# SCH_3Electronic-Trash_2025-03-29.net
KiCad netlist of a schematic drawn in EasyEDA
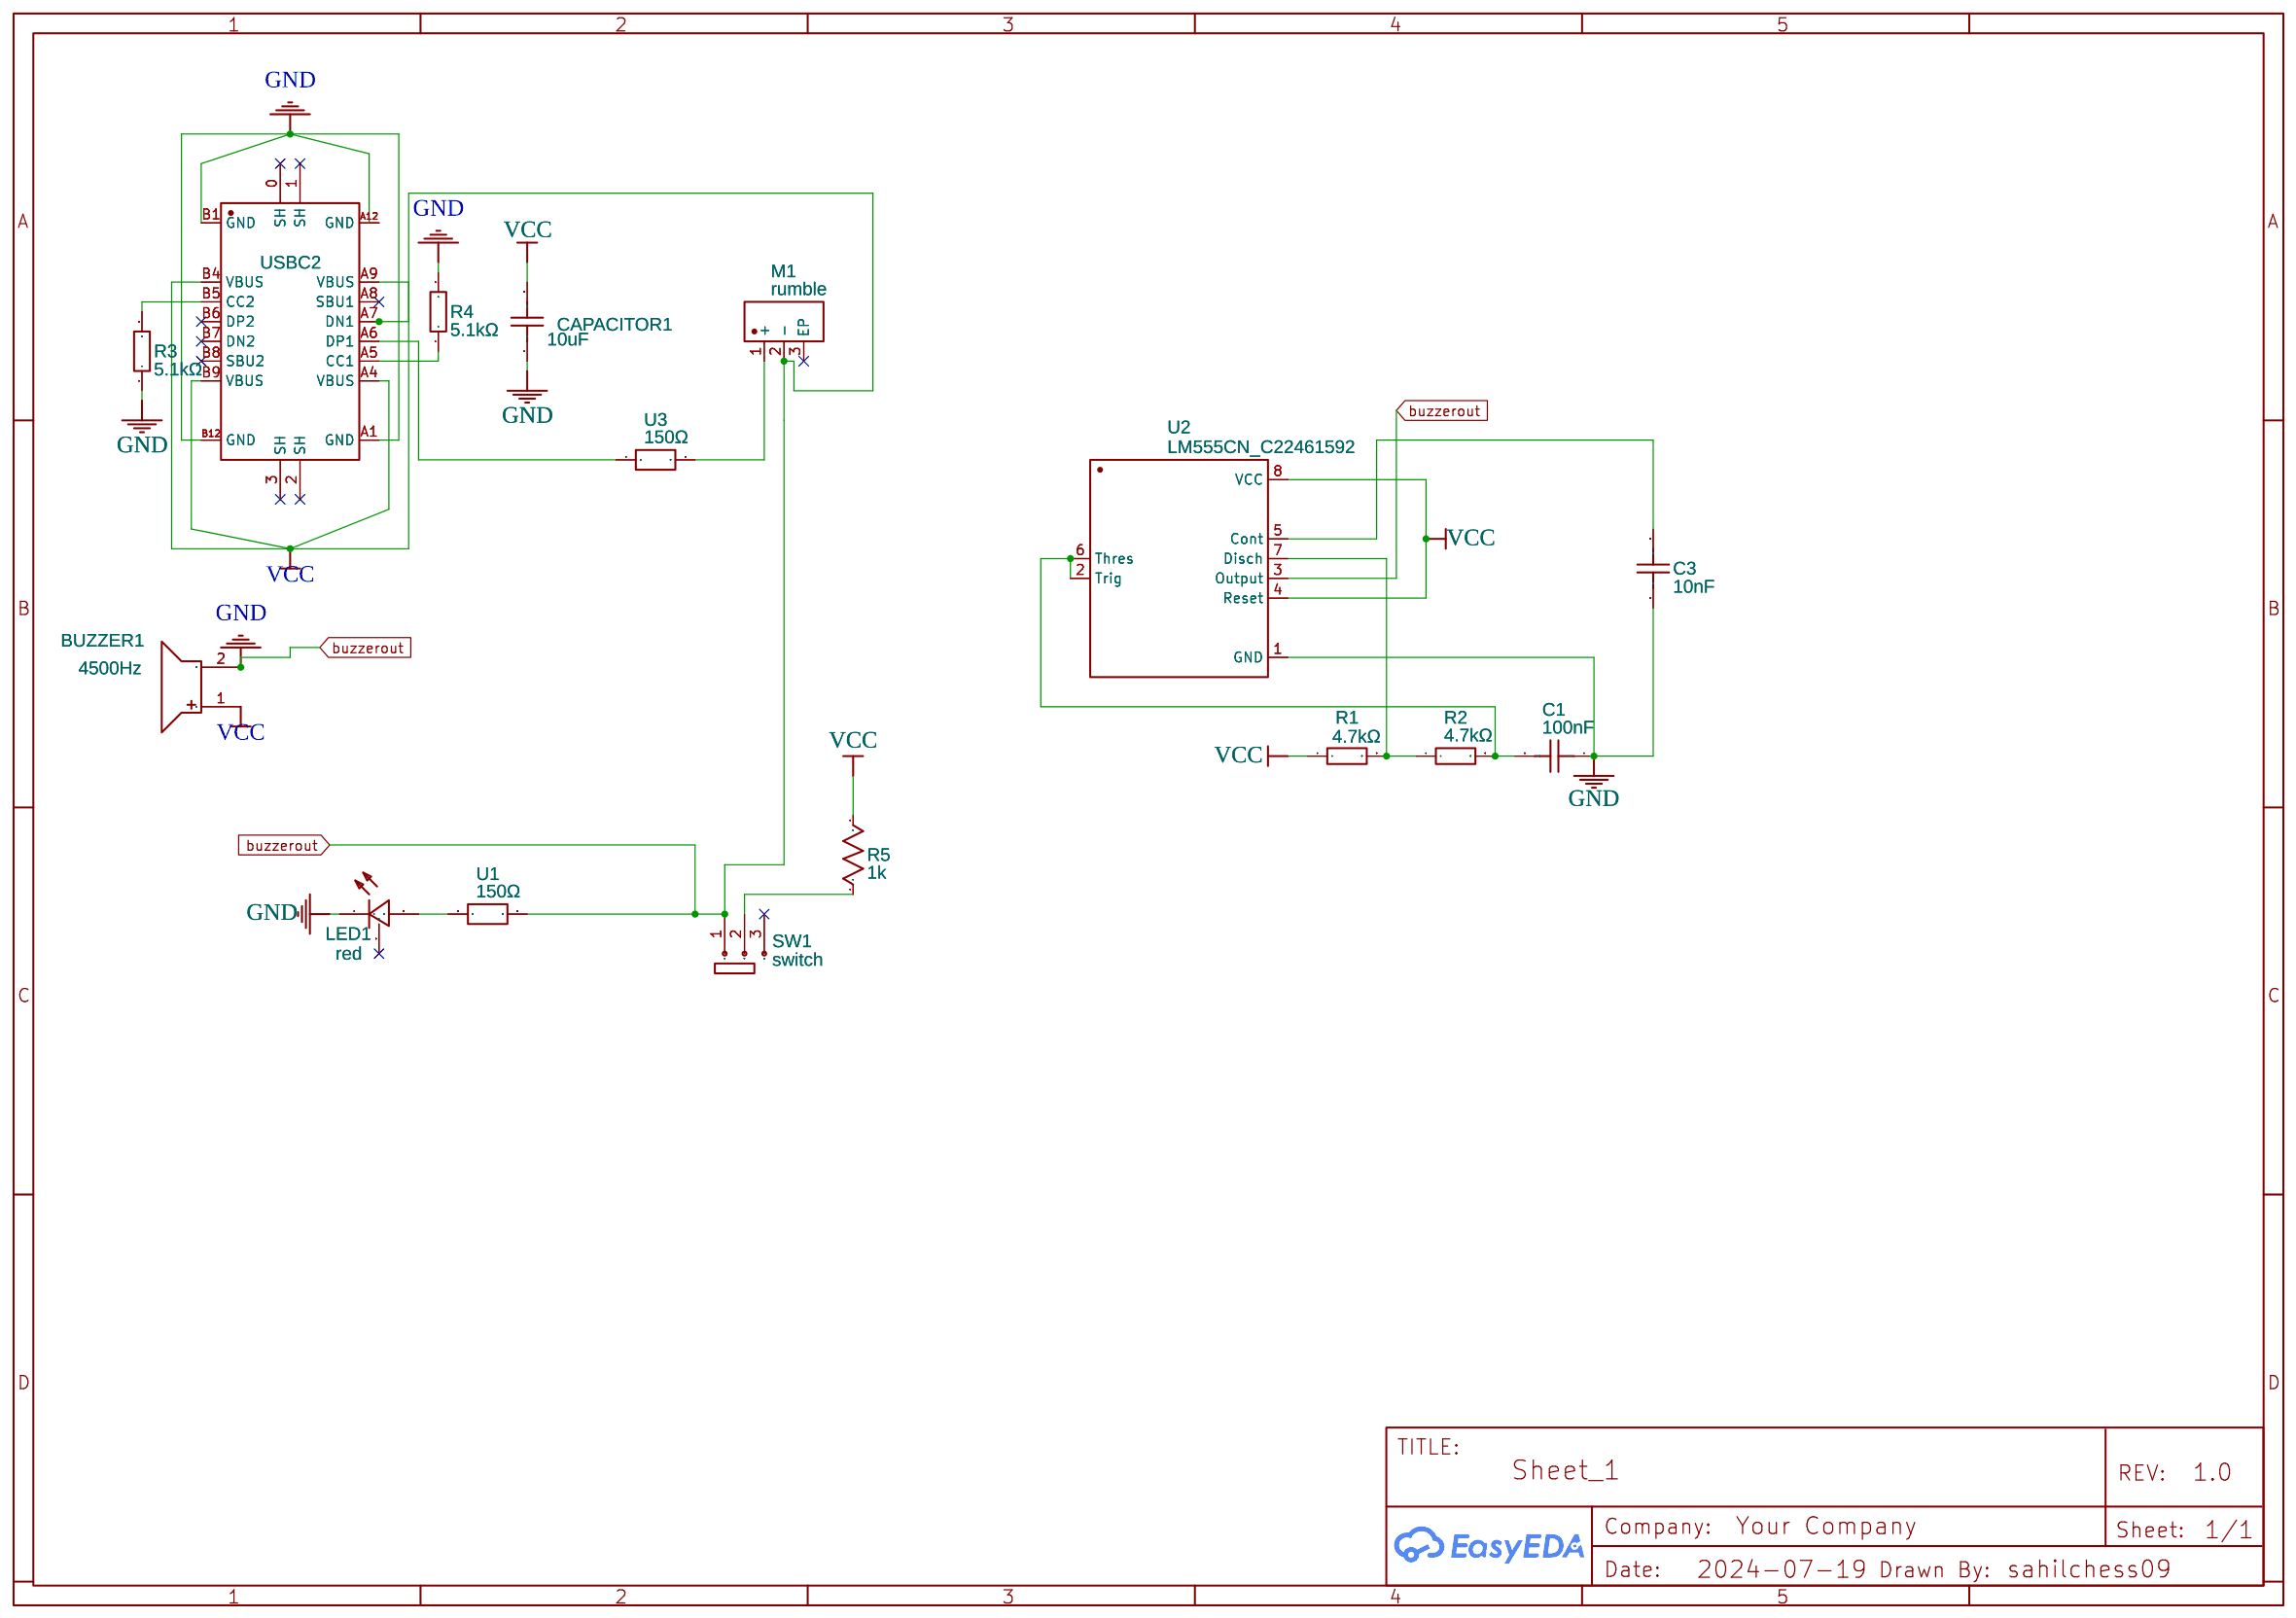
[diagram p0: schematic sheet]

(export (version "E")
  (design (tool "Eeschema 10.0.6"))
  (components
    (comp (ref "BUZZER1")
      (value "4500Hz")
      (fields (field (name "Manufacturer Part") "HND-1407B") (field (name "Manufacturer") "华能"))
      (libsource (lib "") (part "HND-1407B"))
    )
    (comp (ref "C1")
      (value "100nF")
      (fields
        (field (name "Manufacturer Part") "MPX104K31D2KN15800")
        (field (name "Manufacturer") "KNSCHA(科尼盛)")
      )
      (libsource (lib "") (part "MPX104K31D2KN15800"))
    )
    (comp (ref "C3")
      (value "10nF")
      (fields
        (field (name "Manufacturer Part") "B1030630-D-10-3R")
        (field (name "Manufacturer") "GDHY(广东华裕)")
      )
      (libsource (lib "") (part "B1030630-D-10-3R"))
    )
    (comp (ref "CAPACITOR1")
      (value "10uF")
      (fields
        (field (name "Manufacturer Part") "CL10A106KP8NNNC")
        (field (name "Manufacturer") "SAMSUNG(三星)")
      )
      (libsource (lib "") (part "CL10A106KP8NNNC"))
    )
    (comp (ref "LED1")
      (value "red")
      (fields
        (field (name "Manufacturer Part") "TJ-S3210SW5TGLC2R-A5")
        (field (name "Manufacturer") "TOGIALED(统佳)")
      )
      (libsource (lib "") (part "TJ-S3210SW5TGLC2R-A5"))
    )
    (comp (ref "M1")
      (value "rumble")
      (fields (field (name "Manufacturer Part") "Z3OC1T8219731") (field (name "Manufacturer") "KOTL(金龙机电)"))
      (libsource (lib "") (part "Z3OC1T8219731"))
    )
    (comp (ref "R1")
      (value "4.7kΩ")
      (fields
        (field (name "Manufacturer Part") "MF1/4W-4.7KΩ±1% T")
        (field (name "Manufacturer") "CCO(千志电子)")
      )
      (libsource (lib "") (part "MF1/4W-4.7KΩ±1% T52"))
    )
    (comp (ref "R2")
      (value "4.7kΩ")
      (fields
        (field (name "Manufacturer Part") "MF1/4W-4.7KΩ±1% T")
        (field (name "Manufacturer") "CCO(千志电子)")
      )
      (libsource (lib "") (part "MF1/4W-4.7KΩ±1% T52"))
    )
    (comp (ref "R3")
      (value "5.1kΩ")
      (fields (field (name "Manufacturer Part") "RMC08055.1K1%N") (field (name "Manufacturer") "Tyohm(幸亚电阻)"))
      (libsource (lib "") (part "RMC08055.1K1%N"))
    )
    (comp (ref "R4")
      (value "5.1kΩ")
      (fields (field (name "Manufacturer Part") "RMC08055.1K1%N") (field (name "Manufacturer") "Tyohm(幸亚电阻)"))
      (libsource (lib "") (part "RMC08055.1K1%N"))
    )
    (comp (ref "R5") (value "1k") (libsource (lib "") (part "R_0603_US")))
    (comp (ref "SW1")
      (value "switch")
      (fields (field (name "Manufacturer Part") "K3-1235S-L1") (field (name "Manufacturer") "韩国韩荣"))
      (libsource (lib "") (part "K3-1235S-L1"))
    )
    (comp (ref "U1")
      (value "150Ω")
      (fields
        (field (name "Manufacturer Part") "TNPW0402150RBYEP")
        (field (name "Manufacturer") "VISHAY(威世)")
      )
      (libsource (lib "") (part "TNPW0402150RBYEP"))
    )
    (comp (ref "U2")
      (value "LM555CN_C22461592")
      (fields (field (name "Manufacturer Part") "LM555CN") (field (name "Manufacturer") "HGSEMI(华冠)"))
      (libsource (lib "") (part "LM555CN_C22461592"))
    )
    (comp (ref "U3")
      (value "150Ω")
      (fields
        (field (name "Manufacturer Part") "TNPW0402150RBYEP")
        (field (name "Manufacturer") "VISHAY(威世)")
      )
      (libsource (lib "") (part "TNPW0402150RBYEP"))
    )
    (comp (ref "USBC2")
      (value "TYPE-C-31-M-12")
      (fields (field (name "Manufacturer") "韩国韩荣"))
      (libsource (lib "") (part "TYPE-C-31-M-12"))
    )
  )
  (nets
    (net (code "1") (name "Net-(LED1-Pad2)") (class "Default")
      (node (ref "LED1") (pin "2") (pinfunction "2_2") (pintype "unspecified"))
      (node (ref "U1") (pin "1") (pinfunction "1_1") (pintype "unspecified"))
    )
    (net (code "2") (name "Net-(M1-+)") (class "Default")
      (node (ref "M1") (pin "1") (pinfunction "+_1") (pintype "unspecified"))
      (node (ref "U3") (pin "2") (pinfunction "2_2") (pintype "unspecified"))
    )
    (net (code "3") (name "Net-(R5-Pad1)") (class "Default")
      (node (ref "R5") (pin "1") (pinfunction "1_1") (pintype "unspecified"))
      (node (ref "SW1") (pin "2") (pinfunction "2_2") (pintype "unspecified"))
    )
    (net (code "4") (name "Net-(U2-Cont)") (class "Default")
      (node (ref "C3") (pin "2") (pinfunction "2_2") (pintype "unspecified"))
      (node (ref "U2") (pin "5") (pinfunction "Cont_5") (pintype "unspecified"))
    )
    (net (code "5") (name "Net-(U2-Disch)") (class "Default")
      (node (ref "R1") (pin "2") (pinfunction "2_2") (pintype "unspecified"))
      (node (ref "R2") (pin "1") (pinfunction "1_1") (pintype "unspecified"))
      (node (ref "U2") (pin "7") (pinfunction "Disch_7") (pintype "unspecified"))
    )
    (net (code "6") (name "Net-(U2-Thres)") (class "Default")
      (node (ref "C1") (pin "2") (pinfunction "2_2") (pintype "unspecified"))
      (node (ref "R2") (pin "2") (pinfunction "2_2") (pintype "unspecified"))
      (node (ref "U2") (pin "2") (pinfunction "Trig_2") (pintype "unspecified"))
      (node (ref "U2") (pin "6") (pinfunction "Thres_6") (pintype "unspecified"))
    )
    (net (code "7") (name "Net-(USBC2-CC1)") (class "Default")
      (node (ref "R4") (pin "1") (pinfunction "1_1") (pintype "unspecified"))
      (node (ref "USBC2") (pin "A5") (pinfunction "CC1_A5") (pintype "unspecified"))
    )
    (net (code "8") (name "Net-(USBC2-CC2)") (class "Default")
      (node (ref "R3") (pin "2") (pinfunction "2_2") (pintype "unspecified"))
      (node (ref "USBC2") (pin "B5") (pinfunction "CC2_B5") (pintype "unspecified"))
    )
    (net (code "9") (name "Net-(USBC2-DP1)") (class "Default")
      (node (ref "U3") (pin "1") (pinfunction "1_1") (pintype "unspecified"))
      (node (ref "USBC2") (pin "A6") (pinfunction "DP1_A6") (pintype "unspecified"))
    )
    (net (code "10") (name "VCC") (class "Default")
      (node (ref "BUZZER1") (pin "1") (pinfunction "1_1") (pintype "unspecified"))
      (node (ref "CAPACITOR1") (pin "2") (pinfunction "2_2") (pintype "unspecified"))
      (node (ref "R1") (pin "1") (pinfunction "1_1") (pintype "unspecified"))
      (node (ref "R5") (pin "2") (pinfunction "2_2") (pintype "unspecified"))
      (node (ref "U2") (pin "4") (pinfunction "Reset_4") (pintype "unspecified"))
      (node (ref "U2") (pin "8") (pinfunction "VCC_8") (pintype "unspecified"))
      (node (ref "USBC2") (pin "A4") (pinfunction "VBUS_A4") (pintype "unspecified"))
      (node (ref "USBC2") (pin "A9") (pinfunction "VBUS_A9") (pintype "unspecified"))
      (node (ref "USBC2") (pin "B4") (pinfunction "VBUS_B4") (pintype "unspecified"))
      (node (ref "USBC2") (pin "B9") (pinfunction "VBUS_B9") (pintype "unspecified"))
    )
    (net (code "11") (name "buzzerout") (class "Default")
      (node (ref "BUZZER1") (pin "2") (pinfunction "2_2") (pintype "unspecified"))
      (node (ref "C1") (pin "1") (pinfunction "1_1") (pintype "unspecified"))
      (node (ref "C3") (pin "1") (pinfunction "1_1") (pintype "unspecified"))
      (node (ref "CAPACITOR1") (pin "1") (pinfunction "1_1") (pintype "unspecified"))
      (node (ref "LED1") (pin "1") (pinfunction "1_1") (pintype "unspecified"))
      (node (ref "M1") (pin "2") (pinfunction "-_2") (pintype "unspecified"))
      (node (ref "R3") (pin "1") (pinfunction "1_1") (pintype "unspecified"))
      (node (ref "R4") (pin "2") (pinfunction "2_2") (pintype "unspecified"))
      (node (ref "SW1") (pin "1") (pinfunction "1_1") (pintype "unspecified"))
      (node (ref "U1") (pin "2") (pinfunction "2_2") (pintype "unspecified"))
      (node (ref "U2") (pin "1") (pinfunction "GND_1") (pintype "unspecified"))
      (node (ref "U2") (pin "3") (pinfunction "Output_3") (pintype "unspecified"))
      (node (ref "USBC2") (pin "A1") (pinfunction "GND_A1") (pintype "unspecified"))
      (node (ref "USBC2") (pin "A12") (pinfunction "GND_A12") (pintype "unspecified"))
      (node (ref "USBC2") (pin "A7") (pinfunction "DN1_A7") (pintype "unspecified"))
      (node (ref "USBC2") (pin "B1") (pinfunction "GND_B1") (pintype "unspecified"))
      (node (ref "USBC2") (pin "B12") (pinfunction "GND_B12") (pintype "unspecified"))
    )
    (net (code "12") (name "unconnected-(LED1-Pad3)") (class "Default")
      (node (ref "LED1") (pin "3") (pinfunction "3_3") (pintype "unspecified+no_connect"))
    )
    (net (code "13") (name "unconnected-(M1-EP-Pad3)") (class "Default")
      (node (ref "M1") (pin "3") (pinfunction "EP_3") (pintype "unspecified+no_connect"))
    )
    (net (code "14") (name "unconnected-(SW1-Pad3)") (class "Default")
      (node (ref "SW1") (pin "3") (pinfunction "3_3") (pintype "unspecified+no_connect"))
    )
    (net (code "15") (name "unconnected-(USBC2-DN2-PadB7)") (class "Default")
      (node (ref "USBC2") (pin "B7") (pinfunction "DN2_B7") (pintype "unspecified+no_connect"))
    )
    (net (code "16") (name "unconnected-(USBC2-DP2-PadB6)") (class "Default")
      (node (ref "USBC2") (pin "B6") (pinfunction "DP2_B6") (pintype "unspecified+no_connect"))
    )
    (net (code "17") (name "unconnected-(USBC2-SBU1-PadA8)") (class "Default")
      (node (ref "USBC2") (pin "A8") (pinfunction "SBU1_A8") (pintype "unspecified+no_connect"))
    )
    (net (code "18") (name "unconnected-(USBC2-SBU2-PadB8)") (class "Default")
      (node (ref "USBC2") (pin "B8") (pinfunction "SBU2_B8") (pintype "unspecified+no_connect"))
    )
    (net (code "19") (name "unconnected-(USBC2-SH-Pad0)") (class "Default")
      (node (ref "USBC2") (pin "0") (pinfunction "SH_0") (pintype "unspecified+no_connect"))
    )
    (net (code "20") (name "unconnected-(USBC2-SH-Pad1)") (class "Default")
      (node (ref "USBC2") (pin "1") (pinfunction "SH_1") (pintype "unspecified+no_connect"))
    )
    (net (code "21") (name "unconnected-(USBC2-SH-Pad2)") (class "Default")
      (node (ref "USBC2") (pin "2") (pinfunction "SH_2") (pintype "unspecified+no_connect"))
    )
    (net (code "22") (name "unconnected-(USBC2-SH-Pad3)") (class "Default")
      (node (ref "USBC2") (pin "3") (pinfunction "SH_3") (pintype "unspecified+no_connect"))
    )
  )
)
